# loiterboard_new.net
KiCad netlist of a schematic drawn in EAGLE
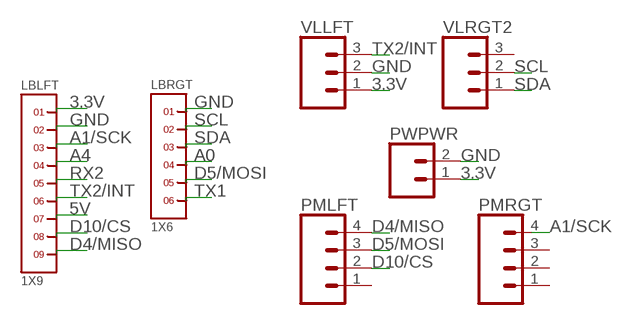
[diagram p0: schematic, sheet 1]

(export (version "E")
  (design (tool "Eeschema 10.0.6"))
  (components
    (comp (ref "LBLFT")
      (value "1X9")
      (footprint "eagle-import:1X9")
      (libsource (lib "eagle-import") (part "1X9"))
    )
    (comp (ref "LBRGT")
      (value "1X6")
      (footprint "eagle-import:1X6")
      (libsource (lib "eagle-import") (part "1X6"))
    )
    (comp (ref "PMLFT")
      (value "CONN_04")
      (footprint "eagle-import:1X04")
      (libsource (lib "eagle-import") (part "CONN_04"))
    )
    (comp (ref "PMRGT")
      (value "CONN_04")
      (footprint "eagle-import:1X04")
      (libsource (lib "eagle-import") (part "CONN_04"))
    )
    (comp (ref "PWPWR")
      (value "CONN_02")
      (footprint "eagle-import:1X02")
      (libsource (lib "eagle-import") (part "CONN_02"))
    )
    (comp (ref "VLLFT")
      (value "CONN_03")
      (footprint "eagle-import:1X03")
      (libsource (lib "eagle-import") (part "CONN_03"))
    )
    (comp (ref "VLRGT2")
      (value "CONN_03")
      (footprint "eagle-import:1X03")
      (libsource (lib "eagle-import") (part "CONN_03"))
    )
  )
  (nets
    (net (code "1") (name "/3.3V") (class "Default")
      (node (ref "LBLFT") (pin "1") (pinfunction "1_1") (pintype "bidirectional"))
      (node (ref "PWPWR") (pin "1") (pinfunction "1_1") (pintype "passive"))
      (node (ref "VLLFT") (pin "1") (pinfunction "1_1") (pintype "passive"))
    )
    (net (code "2") (name "/5V") (class "Default")
      (node (ref "LBLFT") (pin "7") (pinfunction "7_7") (pintype "bidirectional"))
    )
    (net (code "3") (name "/A0") (class "Default")
      (node (ref "LBRGT") (pin "4") (pinfunction "4_4") (pintype "bidirectional"))
    )
    (net (code "4") (name "/A1{slash}SCK") (class "Default")
      (node (ref "LBLFT") (pin "3") (pinfunction "3_3") (pintype "bidirectional"))
      (node (ref "PMRGT") (pin "4") (pinfunction "4_4") (pintype "passive"))
    )
    (net (code "5") (name "/A4") (class "Default")
      (node (ref "LBLFT") (pin "4") (pinfunction "4_4") (pintype "bidirectional"))
    )
    (net (code "6") (name "/D4{slash}MISO") (class "Default")
      (node (ref "LBLFT") (pin "9") (pinfunction "9_9") (pintype "bidirectional"))
      (node (ref "PMLFT") (pin "4") (pinfunction "4_4") (pintype "passive"))
    )
    (net (code "7") (name "/D5{slash}MOSI") (class "Default")
      (node (ref "LBRGT") (pin "5") (pinfunction "5_5") (pintype "bidirectional"))
      (node (ref "PMLFT") (pin "3") (pinfunction "3_3") (pintype "passive"))
    )
    (net (code "8") (name "/D10{slash}CS") (class "Default")
      (node (ref "LBLFT") (pin "8") (pinfunction "8_8") (pintype "bidirectional"))
      (node (ref "PMLFT") (pin "2") (pinfunction "2_2") (pintype "passive"))
    )
    (net (code "9") (name "/GND") (class "Default")
      (node (ref "LBLFT") (pin "2") (pinfunction "2_2") (pintype "bidirectional"))
      (node (ref "LBRGT") (pin "1") (pinfunction "1_1") (pintype "bidirectional"))
      (node (ref "PWPWR") (pin "2") (pinfunction "2_2") (pintype "passive"))
      (node (ref "VLLFT") (pin "2") (pinfunction "2_2") (pintype "passive"))
    )
    (net (code "10") (name "/RX2") (class "Default")
      (node (ref "LBLFT") (pin "5") (pinfunction "5_5") (pintype "bidirectional"))
    )
    (net (code "11") (name "/SCL") (class "Default")
      (node (ref "LBRGT") (pin "2") (pinfunction "2_2") (pintype "bidirectional"))
      (node (ref "VLRGT2") (pin "2") (pinfunction "2_2") (pintype "passive"))
    )
    (net (code "12") (name "/SDA") (class "Default")
      (node (ref "LBRGT") (pin "3") (pinfunction "3_3") (pintype "bidirectional"))
      (node (ref "VLRGT2") (pin "1") (pinfunction "1_1") (pintype "passive"))
    )
    (net (code "13") (name "/TX1") (class "Default")
      (node (ref "LBRGT") (pin "6") (pinfunction "6_6") (pintype "bidirectional"))
    )
    (net (code "14") (name "/TX2{slash}INT") (class "Default")
      (node (ref "LBLFT") (pin "6") (pinfunction "6_6") (pintype "bidirectional"))
      (node (ref "VLLFT") (pin "3") (pinfunction "3_3") (pintype "passive"))
    )
    (net (code "15") (name "unconnected-(PMLFT-Pad1)") (class "Default")
      (node (ref "PMLFT") (pin "1") (pinfunction "1_1") (pintype "passive"))
    )
    (net (code "16") (name "unconnected-(PMRGT-Pad1)") (class "Default")
      (node (ref "PMRGT") (pin "1") (pinfunction "1_1") (pintype "passive"))
    )
    (net (code "17") (name "unconnected-(PMRGT-Pad2)") (class "Default")
      (node (ref "PMRGT") (pin "2") (pinfunction "2_2") (pintype "passive"))
    )
    (net (code "18") (name "unconnected-(PMRGT-Pad3)") (class "Default")
      (node (ref "PMRGT") (pin "3") (pinfunction "3_3") (pintype "passive"))
    )
    (net (code "19") (name "unconnected-(VLRGT2-Pad3)") (class "Default")
      (node (ref "VLRGT2") (pin "3") (pinfunction "3_3") (pintype "passive"))
    )
  )
)
